# PIC.net
KiCad netlist of a schematic drawn in Altium Designer
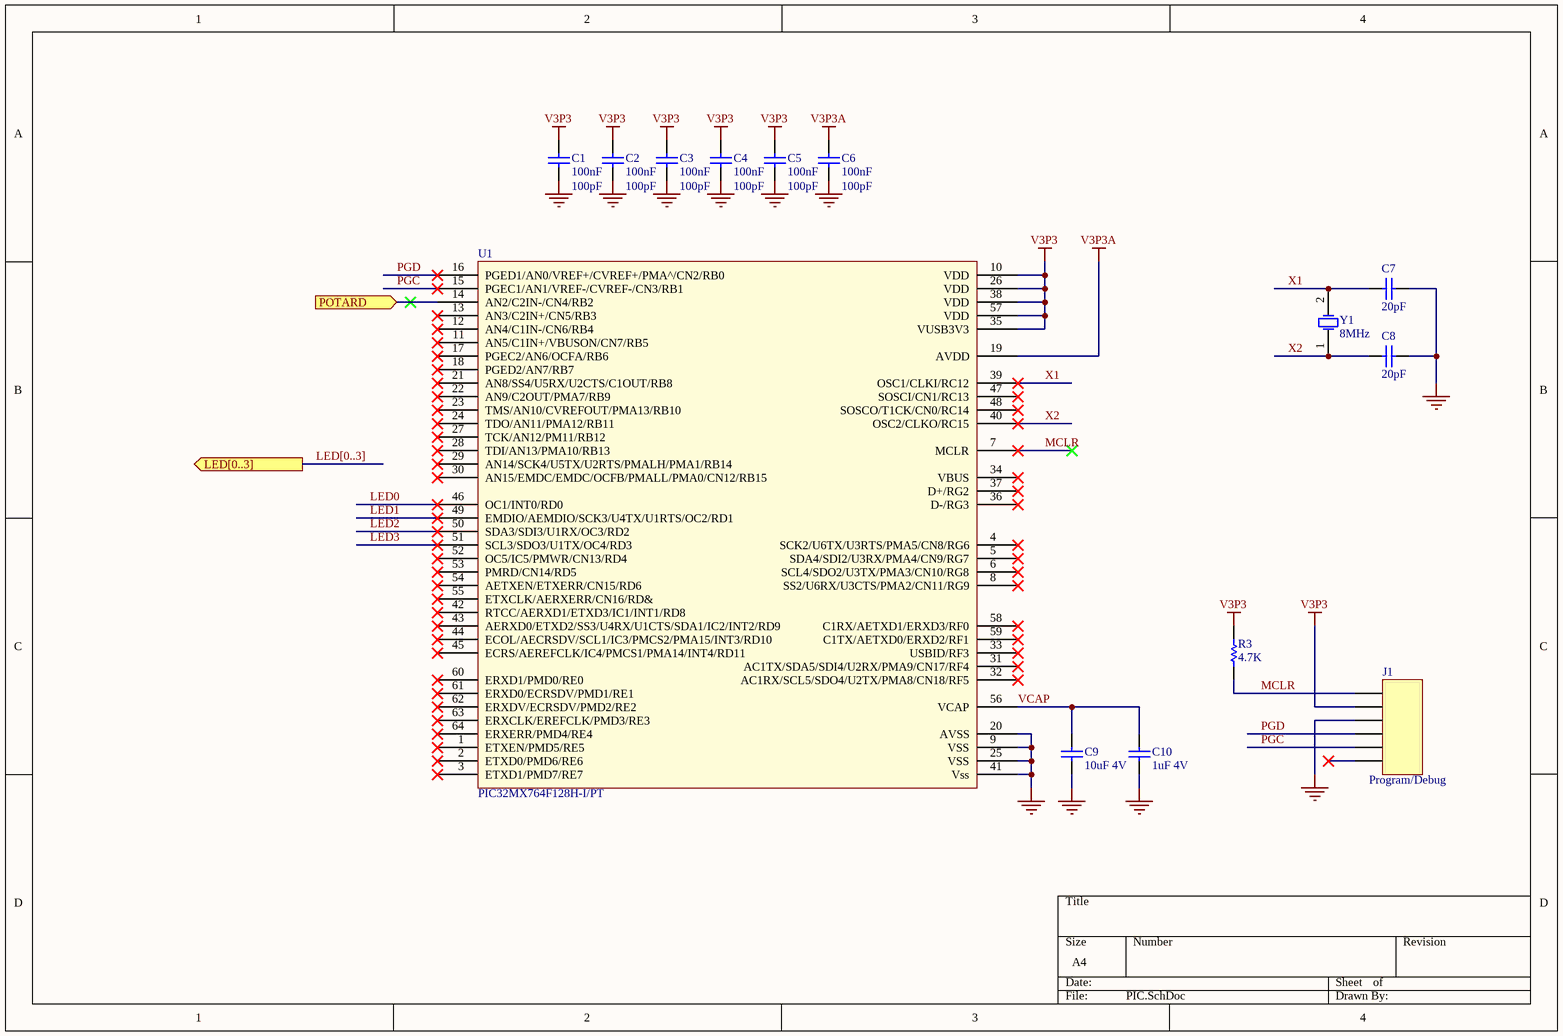
[diagram p0: PIC.SchDoc]

(export (version "E")
  (design (tool "Eeschema 10.0.6"))
  (components
    (comp (ref "C1")
      (value "100nF")
      (footprint "CAPC1608N")
      (description "Capacitor")
      (fields (field (name "VALUE2") "100pF") (field (name "PUBLISHER") "Altium Limited"))
      (libsource (lib "Miscellaneous Devices") (part "Cap"))
    )
    (comp (ref "C2")
      (value "100nF")
      (footprint "CAPC1608N")
      (description "Capacitor")
      (fields (field (name "VALUE2") "100pF") (field (name "PUBLISHER") "Altium Limited"))
      (libsource (lib "Miscellaneous Devices") (part "Cap"))
    )
    (comp (ref "C3")
      (value "100nF")
      (footprint "CAPC1608N")
      (description "Capacitor")
      (fields (field (name "VALUE2") "100pF") (field (name "PUBLISHER") "Altium Limited"))
      (libsource (lib "Miscellaneous Devices") (part "Cap"))
    )
    (comp (ref "C4")
      (value "100nF")
      (footprint "CAPC1608N")
      (description "Capacitor")
      (fields (field (name "VALUE2") "100pF") (field (name "PUBLISHER") "Altium Limited"))
      (libsource (lib "Miscellaneous Devices") (part "Cap"))
    )
    (comp (ref "C5")
      (value "100nF")
      (footprint "CAPC1608N")
      (description "Capacitor")
      (fields (field (name "VALUE2") "100pF") (field (name "PUBLISHER") "Altium Limited"))
      (libsource (lib "Miscellaneous Devices") (part "Cap"))
    )
    (comp (ref "C6")
      (value "100nF")
      (footprint "CAPC1608N")
      (description "Capacitor")
      (fields (field (name "VALUE2") "100pF") (field (name "PUBLISHER") "Altium Limited"))
      (libsource (lib "Miscellaneous Devices") (part "Cap"))
    )
    (comp (ref "C7")
      (value "20pF")
      (footprint "CAPC1608N")
      (description "Capacitor")
      (fields (field (name "PUBLISHER") "Altium Limited"))
      (libsource (lib "Miscellaneous Devices") (part "Cap"))
    )
    (comp (ref "C8")
      (value "20pF")
      (footprint "CAPC1608N")
      (description "Capacitor")
      (fields (field (name "PUBLISHER") "Altium Limited"))
      (libsource (lib "Miscellaneous Devices") (part "Cap"))
    )
    (comp (ref "C9")
      (value "10uF 4V")
      (footprint "CAP2012N")
      (description "Capacitor")
      (fields (field (name "PUBLISHER") "Altium Limited"))
      (libsource (lib "Miscellaneous Devices") (part "Cap"))
    )
    (comp (ref "C10")
      (value "1uF 4V")
      (footprint "CAPC1608N")
      (description "Capacitor")
      (fields (field (name "PUBLISHER") "Altium Limited"))
      (libsource (lib "Miscellaneous Devices") (part "Cap"))
    )
    (comp (ref "J1")
      (value "Comment")
      (footprint "RJ12_90")
      (description "Header, 6-Pin")
      (fields (field (name "TYPE") "Program/Debug") (field (name "PUBLISHER") "Altium Limited"))
      (libsource (lib "Miscellaneous Connectors") (part "Header 6"))
    )
    (comp (ref "R3")
      (value "4.7K")
      (footprint "RESC1608N")
      (description "Resistor")
      (fields (field (name "PUBLISHER") "Altium Limited"))
      (libsource (lib "Miscellaneous Devices") (part "Res1"))
    )
    (comp (ref "U1")
      (value "PIC32MX764F128H-I/PT")
      (footprint "QFP50P1200X1200X120-64")
      (libsource (lib "TP2") (part "Component_1"))
    )
    (comp (ref "Y1")
      (value "8MHz")
      (footprint "4H_SMX_CRYSTAL")
      (description "Crystal Oscillator")
      (fields (field (name "PUBLISHER") "Altium Limited"))
      (libsource (lib "Miscellaneous Devices") (part "XTAL"))
    )
  )
  (nets
    (net (code "1") (name "/LED0") (class "Default")
      (node (ref "U1") (pin "46") (pinfunction "OC1/INT0/RD0_46") (pintype "passive+no_connect"))
    )
    (net (code "2") (name "/LED1") (class "Default")
      (node (ref "U1") (pin "49") (pinfunction "EMDIO/AEMDIO/SCK3/U4TX/U1RTS/OC2/RD1_49") (pintype "passive+no_connect"))
    )
    (net (code "3") (name "/LED2") (class "Default")
      (node (ref "U1") (pin "50") (pinfunction "SDA3/SDI3/U1RX/OC3/RD2_50") (pintype "passive+no_connect"))
    )
    (net (code "4") (name "/LED3") (class "Default")
      (node (ref "U1") (pin "51") (pinfunction "SCL3/SDO3/U1TX/OC4/RD3_51") (pintype "passive+no_connect"))
    )
    (net (code "6") (name "/MCLR") (class "Default")
      (node (ref "J1") (pin "1") (pintype "passive"))
      (node (ref "R3") (pin "1") (pinfunction "1_1") (pintype "passive"))
      (node (ref "U1") (pin "7") (pinfunction "MCLR_7") (pintype "passive"))
    )
    (net (code "7") (name "/PGC") (class "Default")
      (node (ref "J1") (pin "5") (pintype "passive"))
      (node (ref "U1") (pin "15") (pinfunction "PGEC1/AN1/VREF-/CVREF-/CN3/RB1_15") (pintype "passive"))
    )
    (net (code "8") (name "/PGD") (class "Default")
      (node (ref "J1") (pin "4") (pintype "passive"))
      (node (ref "U1") (pin "16") (pinfunction "PGED1/AN0/VREF+/CVREF+/PMA^/CN2/RB0_16") (pintype "passive"))
    )
    (net (code "9") (name "/POTARD") (class "Default")
      (node (ref "U1") (pin "14") (pinfunction "AN2/C2IN-/CN4/RB2_14") (pintype "passive+no_connect"))
    )
    (net (code "10") (name "/VCAP") (class "Default")
      (node (ref "C10") (pin "2") (pinfunction "2_2") (pintype "passive"))
      (node (ref "C9") (pin "2") (pinfunction "2_2") (pintype "passive"))
      (node (ref "U1") (pin "56") (pinfunction "VCAP_56") (pintype "passive"))
    )
    (net (code "11") (name "/X1") (class "Default")
      (node (ref "C7") (pin "1") (pinfunction "1_1") (pintype "passive"))
      (node (ref "U1") (pin "39") (pinfunction "OSC1/CLKI/RC12_39") (pintype "passive"))
      (node (ref "Y1") (pin "2") (pinfunction "OSC2_2") (pintype "passive"))
    )
    (net (code "12") (name "/X2") (class "Default")
      (node (ref "C8") (pin "1") (pinfunction "1_1") (pintype "passive"))
      (node (ref "U1") (pin "40") (pinfunction "OSC2/CLKO/RC15_40") (pintype "passive"))
      (node (ref "Y1") (pin "1") (pinfunction "OSC1_1") (pintype "passive"))
    )
    (net (code "13") (name "GND") (class "Default")
      (node (ref "C1") (pin "2") (pinfunction "2_2") (pintype "passive"))
      (node (ref "C10") (pin "1") (pinfunction "1_1") (pintype "passive"))
      (node (ref "C2") (pin "2") (pinfunction "2_2") (pintype "passive"))
      (node (ref "C3") (pin "2") (pinfunction "2_2") (pintype "passive"))
      (node (ref "C4") (pin "2") (pinfunction "2_2") (pintype "passive"))
      (node (ref "C5") (pin "2") (pinfunction "2_2") (pintype "passive"))
      (node (ref "C6") (pin "2") (pinfunction "2_2") (pintype "passive"))
      (node (ref "C7") (pin "2") (pinfunction "2_2") (pintype "passive"))
      (node (ref "C8") (pin "2") (pinfunction "2_2") (pintype "passive"))
      (node (ref "C9") (pin "1") (pinfunction "1_1") (pintype "passive"))
      (node (ref "J1") (pin "3") (pintype "passive"))
      (node (ref "U1") (pin "20") (pinfunction "AVSS_20") (pintype "passive"))
      (node (ref "U1") (pin "25") (pinfunction "VSS_25") (pintype "passive"))
      (node (ref "U1") (pin "41") (pinfunction "Vss_41") (pintype "passive"))
      (node (ref "U1") (pin "9") (pinfunction "VSS_9") (pintype "passive"))
    )
    (net (code "14") (name "V3P3") (class "Default")
      (node (ref "C1") (pin "1") (pinfunction "1_1") (pintype "passive"))
      (node (ref "C2") (pin "1") (pinfunction "1_1") (pintype "passive"))
      (node (ref "C3") (pin "1") (pinfunction "1_1") (pintype "passive"))
      (node (ref "C4") (pin "1") (pinfunction "1_1") (pintype "passive"))
      (node (ref "C5") (pin "1") (pinfunction "1_1") (pintype "passive"))
      (node (ref "J1") (pin "2") (pintype "passive"))
      (node (ref "R3") (pin "2") (pinfunction "2_2") (pintype "passive"))
      (node (ref "U1") (pin "10") (pinfunction "VDD_10") (pintype "passive"))
      (node (ref "U1") (pin "26") (pinfunction "VDD_26") (pintype "passive"))
      (node (ref "U1") (pin "35") (pinfunction "VUSB3V3_35") (pintype "passive"))
      (node (ref "U1") (pin "38") (pinfunction "VDD_38") (pintype "passive"))
      (node (ref "U1") (pin "57") (pinfunction "VDD_57") (pintype "passive"))
    )
    (net (code "15") (name "V3P3A") (class "Default")
      (node (ref "C6") (pin "1") (pinfunction "1_1") (pintype "passive"))
      (node (ref "U1") (pin "19") (pinfunction "AVDD_19") (pintype "passive"))
    )
    (net (code "16") (name "unconnected-(J1-Pad6)") (class "Default")
      (node (ref "J1") (pin "6") (pintype "passive+no_connect"))
    )
    (net (code "17") (name "unconnected-(U1-AC1RX{slash}SCL5{slash}SDO4{slash}U2TX{slash}PMA8{slash}CN18{slash}RF5-Pad32)") (class "Default")
      (node (ref "U1") (pin "32") (pinfunction "AC1RX/SCL5/SDO4/U2TX/PMA8/CN18/RF5_32") (pintype "passive+no_connect"))
    )
    (net (code "18") (name "unconnected-(U1-AC1TX{slash}SDA5{slash}SDI4{slash}U2RX{slash}PMA9{slash}CN17{slash}RF4-Pad31)") (class "Default")
      (node (ref "U1") (pin "31") (pinfunction "AC1TX/SDA5/SDI4/U2RX/PMA9/CN17/RF4_31") (pintype "passive+no_connect"))
    )
    (net (code "19") (name "unconnected-(U1-AERXD0{slash}ETXD2{slash}SS3{slash}U4RX{slash}U1CTS{slash}SDA1{slash}IC2{slash}INT2{slash}RD9-Pad43)") (class "Default")
      (node (ref "U1") (pin "43") (pinfunction "AERXD0/ETXD2/SS3/U4RX/U1CTS/SDA1/IC2/INT2/RD9_43") (pintype "passive+no_connect"))
    )
    (net (code "20") (name "unconnected-(U1-AETXEN{slash}ETXERR{slash}CN15{slash}RD6-Pad54)") (class "Default")
      (node (ref "U1") (pin "54") (pinfunction "AETXEN/ETXERR/CN15/RD6_54") (pintype "passive+no_connect"))
    )
    (net (code "21") (name "unconnected-(U1-AN3{slash}C2IN+{slash}CN5{slash}RB3-Pad13)") (class "Default")
      (node (ref "U1") (pin "13") (pinfunction "AN3/C2IN+/CN5/RB3_13") (pintype "passive+no_connect"))
    )
    (net (code "22") (name "unconnected-(U1-AN4{slash}C1IN-{slash}CN6{slash}RB4-Pad12)") (class "Default")
      (node (ref "U1") (pin "12") (pinfunction "AN4/C1IN-/CN6/RB4_12") (pintype "passive+no_connect"))
    )
    (net (code "23") (name "unconnected-(U1-AN5{slash}C1IN+{slash}VBUSON{slash}CN7{slash}RB5-Pad11)") (class "Default")
      (node (ref "U1") (pin "11") (pinfunction "AN5/C1IN+/VBUSON/CN7/RB5_11") (pintype "passive+no_connect"))
    )
    (net (code "24") (name "unconnected-(U1-AN8{slash}SS4{slash}U5RX{slash}U2CTS{slash}C1OUT{slash}RB8-Pad21)") (class "Default")
      (node (ref "U1") (pin "21") (pinfunction "AN8/SS4/U5RX/U2CTS/C1OUT/RB8_21") (pintype "passive+no_connect"))
    )
    (net (code "25") (name "unconnected-(U1-AN9{slash}C2OUT{slash}PMA7{slash}RB9-Pad22)") (class "Default")
      (node (ref "U1") (pin "22") (pinfunction "AN9/C2OUT/PMA7/RB9_22") (pintype "passive+no_connect"))
    )
    (net (code "26") (name "unconnected-(U1-AN14{slash}SCK4{slash}U5TX{slash}U2RTS{slash}PMALH{slash}PMA1{slash}RB14-Pad29)") (class "Default")
      (node (ref "U1") (pin "29") (pinfunction "AN14/SCK4/U5TX/U2RTS/PMALH/PMA1/RB14_29") (pintype "passive+no_connect"))
    )
    (net (code "27") (name "unconnected-(U1-AN15{slash}EMDC{slash}EMDC{slash}OCFB{slash}PMALL{slash}PMA0{slash}CN12{slash}RB15-Pad30)") (class "Default")
      (node (ref "U1") (pin "30") (pinfunction "AN15/EMDC/EMDC/OCFB/PMALL/PMA0/CN12/RB15_30") (pintype "passive+no_connect"))
    )
    (net (code "28") (name "unconnected-(U1-C1RX{slash}AETXD1{slash}ERXD3{slash}RF0-Pad58)") (class "Default")
      (node (ref "U1") (pin "58") (pinfunction "C1RX/AETXD1/ERXD3/RF0_58") (pintype "passive+no_connect"))
    )
    (net (code "29") (name "unconnected-(U1-C1TX{slash}AETXD0{slash}ERXD2{slash}RF1-Pad59)") (class "Default")
      (node (ref "U1") (pin "59") (pinfunction "C1TX/AETXD0/ERXD2/RF1_59") (pintype "passive+no_connect"))
    )
    (net (code "30") (name "unconnected-(U1-D+{slash}RG2-Pad37)") (class "Default")
      (node (ref "U1") (pin "37") (pinfunction "D+/RG2_37") (pintype "passive+no_connect"))
    )
    (net (code "31") (name "unconnected-(U1-D-{slash}RG3-Pad36)") (class "Default")
      (node (ref "U1") (pin "36") (pinfunction "D-/RG3_36") (pintype "passive+no_connect"))
    )
    (net (code "32") (name "unconnected-(U1-ECOL{slash}AECRSDV{slash}SCL1{slash}IC3{slash}PMCS2{slash}PMA15{slash}INT3{slash}RD10-Pad44)") (class "Default")
      (node (ref "U1") (pin "44") (pinfunction "ECOL/AECRSDV/SCL1/IC3/PMCS2/PMA15/INT3/RD10_44") (pintype "passive+no_connect"))
    )
    (net (code "33") (name "unconnected-(U1-ECRS{slash}AEREFCLK{slash}IC4{slash}PMCS1{slash}PMA14{slash}INT4{slash}RD11-Pad45)") (class "Default")
      (node (ref "U1") (pin "45") (pinfunction "ECRS/AEREFCLK/IC4/PMCS1/PMA14/INT4/RD11_45") (pintype "passive+no_connect"))
    )
    (net (code "34") (name "unconnected-(U1-ERXCLK{slash}EREFCLK{slash}PMD3{slash}RE3-Pad63)") (class "Default")
      (node (ref "U1") (pin "63") (pinfunction "ERXCLK/EREFCLK/PMD3/RE3_63") (pintype "passive+no_connect"))
    )
    (net (code "35") (name "unconnected-(U1-ERXD0{slash}ECRSDV{slash}PMD1{slash}RE1-Pad61)") (class "Default")
      (node (ref "U1") (pin "61") (pinfunction "ERXD0/ECRSDV/PMD1/RE1_61") (pintype "passive+no_connect"))
    )
    (net (code "36") (name "unconnected-(U1-ERXD1{slash}PMD0{slash}RE0-Pad60)") (class "Default")
      (node (ref "U1") (pin "60") (pinfunction "ERXD1/PMD0/RE0_60") (pintype "passive+no_connect"))
    )
    (net (code "37") (name "unconnected-(U1-ERXDV{slash}ECRSDV{slash}PMD2{slash}RE2-Pad62)") (class "Default")
      (node (ref "U1") (pin "62") (pinfunction "ERXDV/ECRSDV/PMD2/RE2_62") (pintype "passive+no_connect"))
    )
    (net (code "38") (name "unconnected-(U1-ERXERR{slash}PMD4{slash}RE4-Pad64)") (class "Default")
      (node (ref "U1") (pin "64") (pinfunction "ERXERR/PMD4/RE4_64") (pintype "passive+no_connect"))
    )
    (net (code "39") (name "unconnected-(U1-ETXCLK{slash}AERXERR{slash}CN16{slash}RD&-Pad55)") (class "Default")
      (node (ref "U1") (pin "55") (pinfunction "ETXCLK/AERXERR/CN16/RD&_55") (pintype "passive+no_connect"))
    )
    (net (code "40") (name "unconnected-(U1-ETXD0{slash}PMD6{slash}RE6-Pad2)") (class "Default")
      (node (ref "U1") (pin "2") (pinfunction "ETXD0/PMD6/RE6_2") (pintype "passive+no_connect"))
    )
    (net (code "41") (name "unconnected-(U1-ETXD1{slash}PMD7{slash}RE7-Pad3)") (class "Default")
      (node (ref "U1") (pin "3") (pinfunction "ETXD1/PMD7/RE7_3") (pintype "passive+no_connect"))
    )
    (net (code "42") (name "unconnected-(U1-ETXEN{slash}PMD5{slash}RE5-Pad1)") (class "Default")
      (node (ref "U1") (pin "1") (pinfunction "ETXEN/PMD5/RE5_1") (pintype "passive+no_connect"))
    )
    (net (code "43") (name "unconnected-(U1-OC5{slash}IC5{slash}PMWR{slash}CN13{slash}RD4-Pad52)") (class "Default")
      (node (ref "U1") (pin "52") (pinfunction "OC5/IC5/PMWR/CN13/RD4_52") (pintype "passive+no_connect"))
    )
    (net (code "44") (name "unconnected-(U1-PGEC2{slash}AN6{slash}OCFA{slash}RB6-Pad17)") (class "Default")
      (node (ref "U1") (pin "17") (pinfunction "PGEC2/AN6/OCFA/RB6_17") (pintype "passive+no_connect"))
    )
    (net (code "45") (name "unconnected-(U1-PGED2{slash}AN7{slash}RB7-Pad18)") (class "Default")
      (node (ref "U1") (pin "18") (pinfunction "PGED2/AN7/RB7_18") (pintype "passive+no_connect"))
    )
    (net (code "46") (name "unconnected-(U1-PMRD{slash}CN14{slash}RD5-Pad53)") (class "Default")
      (node (ref "U1") (pin "53") (pinfunction "PMRD/CN14/RD5_53") (pintype "passive+no_connect"))
    )
    (net (code "47") (name "unconnected-(U1-RTCC{slash}AERXD1{slash}ETXD3{slash}IC1{slash}INT1{slash}RD8-Pad42)") (class "Default")
      (node (ref "U1") (pin "42") (pinfunction "RTCC/AERXD1/ETXD3/IC1/INT1/RD8_42") (pintype "passive+no_connect"))
    )
    (net (code "48") (name "unconnected-(U1-SCK2{slash}U6TX{slash}U3RTS{slash}PMA5{slash}CN8{slash}RG6-Pad4)") (class "Default")
      (node (ref "U1") (pin "4") (pinfunction "SCK2/U6TX/U3RTS/PMA5/CN8/RG6_4") (pintype "passive+no_connect"))
    )
    (net (code "49") (name "unconnected-(U1-SCL4{slash}SDO2{slash}U3TX{slash}PMA3{slash}CN10{slash}RG8-Pad6)") (class "Default")
      (node (ref "U1") (pin "6") (pinfunction "SCL4/SDO2/U3TX/PMA3/CN10/RG8_6") (pintype "passive+no_connect"))
    )
    (net (code "50") (name "unconnected-(U1-SDA4{slash}SDI2{slash}U3RX{slash}PMA4{slash}CN9{slash}RG7-Pad5)") (class "Default")
      (node (ref "U1") (pin "5") (pinfunction "SDA4/SDI2/U3RX/PMA4/CN9/RG7_5") (pintype "passive+no_connect"))
    )
    (net (code "51") (name "unconnected-(U1-SOSCI{slash}CN1{slash}RC13-Pad47)") (class "Default")
      (node (ref "U1") (pin "47") (pinfunction "SOSCI/CN1/RC13_47") (pintype "passive+no_connect"))
    )
    (net (code "52") (name "unconnected-(U1-SOSCO{slash}T1CK{slash}CN0{slash}RC14-Pad48)") (class "Default")
      (node (ref "U1") (pin "48") (pinfunction "SOSCO/T1CK/CN0/RC14_48") (pintype "passive+no_connect"))
    )
    (net (code "53") (name "unconnected-(U1-SS2{slash}U6RX{slash}U3CTS{slash}PMA2{slash}CN11{slash}RG9-Pad8)") (class "Default")
      (node (ref "U1") (pin "8") (pinfunction "SS2/U6RX/U3CTS/PMA2/CN11/RG9_8") (pintype "passive+no_connect"))
    )
    (net (code "54") (name "unconnected-(U1-TCK{slash}AN12{slash}PM11{slash}RB12-Pad27)") (class "Default")
      (node (ref "U1") (pin "27") (pinfunction "TCK/AN12/PM11/RB12_27") (pintype "passive+no_connect"))
    )
    (net (code "55") (name "unconnected-(U1-TDI{slash}AN13{slash}PMA10{slash}RB13-Pad28)") (class "Default")
      (node (ref "U1") (pin "28") (pinfunction "TDI/AN13/PMA10/RB13_28") (pintype "passive+no_connect"))
    )
    (net (code "56") (name "unconnected-(U1-TDO{slash}AN11{slash}PMA12{slash}RB11-Pad24)") (class "Default")
      (node (ref "U1") (pin "24") (pinfunction "TDO/AN11/PMA12/RB11_24") (pintype "passive+no_connect"))
    )
    (net (code "57") (name "unconnected-(U1-TMS{slash}AN10{slash}CVREFOUT{slash}PMA13{slash}RB10-Pad23)") (class "Default")
      (node (ref "U1") (pin "23") (pinfunction "TMS/AN10/CVREFOUT/PMA13/RB10_23") (pintype "passive+no_connect"))
    )
    (net (code "58") (name "unconnected-(U1-USBID{slash}RF3-Pad33)") (class "Default")
      (node (ref "U1") (pin "33") (pinfunction "USBID/RF3_33") (pintype "passive+no_connect"))
    )
    (net (code "59") (name "unconnected-(U1-VBUS-Pad34)") (class "Default")
      (node (ref "U1") (pin "34") (pinfunction "VBUS_34") (pintype "passive+no_connect"))
    )
  )
)
